# gambar.net
KiCad netlist of a schematic drawn in EAGLE
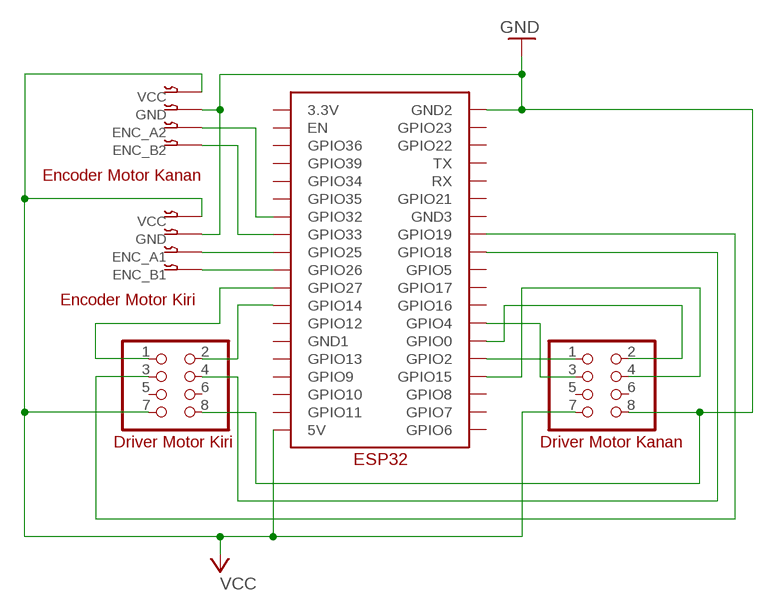
[diagram p0: schematic, sheet 1]

(export (version "E")
  (design (tool "Eeschema 10.0.6"))
  (components
    (comp (ref "DRIV1")
      (value "PINHD-2X4")
      (footprint "eagle-import:2X04")
      (libsource (lib "eagle-import") (part "PINHD-2X4"))
    )
    (comp (ref "DRIV2")
      (value "PINHD-2X4")
      (footprint "eagle-import:2X04")
      (libsource (lib "eagle-import") (part "PINHD-2X4"))
    )
    (comp (ref "U$1")
      (value "ESP32_GRBL")
      (footprint "eagle-import:ESP32_GRBL")
      (libsource (lib "eagle-import") (part "ESP32_GRBL"))
    )
    (comp (ref "X1")
      (value "ENC1")
      (footprint "eagle-import:B4B-XH")
      (libsource (lib "eagle-import") (part "04-JST-B4B-XH-A"))
    )
    (comp (ref "X2")
      (value "ENC2")
      (footprint "eagle-import:B4B-XH")
      (libsource (lib "eagle-import") (part "04-JST-B4B-XH-A"))
    )
  )
  (nets
    (net (code "1") (name "/ENC_A1") (class "Default")
      (node (ref "U$1") (pin "GPIO25") (pinfunction "GPIO25_GPIO25") (pintype "bidirectional"))
      (node (ref "X2") (pin "P$3") (pinfunction "1_P$3") (pintype "passive"))
    )
    (net (code "2") (name "/ENC_A2") (class "Default")
      (node (ref "U$1") (pin "GPIO32") (pinfunction "GPIO32_GPIO32") (pintype "bidirectional"))
      (node (ref "X1") (pin "P$3") (pinfunction "1_P$3") (pintype "passive"))
    )
    (net (code "3") (name "/ENC_B1") (class "Default")
      (node (ref "U$1") (pin "GPIO26") (pinfunction "GPIO26_GPIO26") (pintype "bidirectional"))
      (node (ref "X2") (pin "P$4") (pinfunction "1_P$4") (pintype "passive"))
    )
    (net (code "4") (name "/ENC_B2") (class "Default")
      (node (ref "U$1") (pin "GPIO33") (pinfunction "GPIO33_GPIO33") (pintype "bidirectional"))
      (node (ref "X1") (pin "P$4") (pinfunction "1_P$4") (pintype "passive"))
    )
    (net (code "5") (name "GND") (class "Default")
      (node (ref "DRIV1") (pin "8") (pinfunction "8_8") (pintype "passive"))
      (node (ref "DRIV2") (pin "8") (pinfunction "8_8") (pintype "passive"))
      (node (ref "U$1") (pin "GND2") (pinfunction "GND2_GND2") (pintype "bidirectional"))
      (node (ref "X1") (pin "P$2") (pinfunction "1_P$2") (pintype "passive"))
      (node (ref "X2") (pin "P$2") (pinfunction "1_P$2") (pintype "passive"))
    )
    (net (code "6") (name "Net-(DRIV1-Pad1)") (class "Default")
      (node (ref "DRIV1") (pin "1") (pinfunction "1_1") (pintype "passive"))
      (node (ref "U$1") (pin "GPIO27") (pinfunction "GPIO27_GPIO27") (pintype "bidirectional"))
    )
    (net (code "7") (name "Net-(DRIV1-Pad2)") (class "Default")
      (node (ref "DRIV1") (pin "2") (pinfunction "2_2") (pintype "passive"))
      (node (ref "U$1") (pin "GPIO14") (pinfunction "GPIO14_GPIO14") (pintype "bidirectional"))
    )
    (net (code "8") (name "Net-(DRIV1-Pad3)") (class "Default")
      (node (ref "DRIV1") (pin "3") (pinfunction "3_3") (pintype "passive"))
      (node (ref "U$1") (pin "GPIO19") (pinfunction "GPIO19_GPIO19") (pintype "bidirectional"))
    )
    (net (code "9") (name "Net-(DRIV1-Pad4)") (class "Default")
      (node (ref "DRIV1") (pin "4") (pinfunction "4_4") (pintype "passive"))
      (node (ref "U$1") (pin "GPIO18") (pinfunction "GPIO18_GPIO18") (pintype "bidirectional"))
    )
    (net (code "10") (name "Net-(DRIV2-Pad1)") (class "Default")
      (node (ref "DRIV2") (pin "1") (pinfunction "1_1") (pintype "passive"))
      (node (ref "U$1") (pin "GPIO2") (pinfunction "GPIO2_GPIO2") (pintype "bidirectional"))
    )
    (net (code "11") (name "Net-(DRIV2-Pad2)") (class "Default")
      (node (ref "DRIV2") (pin "2") (pinfunction "2_2") (pintype "passive"))
      (node (ref "U$1") (pin "GPIO0") (pinfunction "GPIO0_GPIO0") (pintype "bidirectional"))
    )
    (net (code "12") (name "Net-(DRIV2-Pad3)") (class "Default")
      (node (ref "DRIV2") (pin "3") (pinfunction "3_3") (pintype "passive"))
      (node (ref "U$1") (pin "GPIO4") (pinfunction "GPIO4_GPIO4") (pintype "bidirectional"))
    )
    (net (code "13") (name "Net-(DRIV2-Pad4)") (class "Default")
      (node (ref "DRIV2") (pin "4") (pinfunction "4_4") (pintype "passive"))
      (node (ref "U$1") (pin "GPIO15") (pinfunction "GPIO15_GPIO15") (pintype "bidirectional"))
    )
    (net (code "14") (name "VCC") (class "Default")
      (node (ref "DRIV1") (pin "7") (pinfunction "7_7") (pintype "passive"))
      (node (ref "DRIV2") (pin "7") (pinfunction "7_7") (pintype "passive"))
      (node (ref "U$1") (pin "5V") (pinfunction "5V_5V") (pintype "bidirectional"))
      (node (ref "X1") (pin "P$1") (pinfunction "1_P$1") (pintype "passive"))
      (node (ref "X2") (pin "P$1") (pinfunction "1_P$1") (pintype "passive"))
    )
    (net (code "15") (name "unconnected-(DRIV1-Pad5)") (class "Default")
      (node (ref "DRIV1") (pin "5") (pinfunction "5_5") (pintype "passive"))
    )
    (net (code "16") (name "unconnected-(DRIV1-Pad6)") (class "Default")
      (node (ref "DRIV1") (pin "6") (pinfunction "6_6") (pintype "passive"))
    )
    (net (code "17") (name "unconnected-(DRIV2-Pad5)") (class "Default")
      (node (ref "DRIV2") (pin "5") (pinfunction "5_5") (pintype "passive"))
    )
    (net (code "18") (name "unconnected-(DRIV2-Pad6)") (class "Default")
      (node (ref "DRIV2") (pin "6") (pinfunction "6_6") (pintype "passive"))
    )
    (net (code "19") (name "unconnected-(U$1-Pad3.3V)") (class "Default")
      (node (ref "U$1") (pin "3.3V") (pinfunction "3.3V_3.3V") (pintype "bidirectional"))
    )
    (net (code "20") (name "unconnected-(U$1-PadEN)") (class "Default")
      (node (ref "U$1") (pin "EN") (pinfunction "EN_EN") (pintype "bidirectional"))
    )
    (net (code "21") (name "unconnected-(U$1-PadGND1)") (class "Default")
      (node (ref "U$1") (pin "GND1") (pinfunction "GND1_GND1") (pintype "bidirectional"))
    )
    (net (code "22") (name "unconnected-(U$1-PadGND3)") (class "Default")
      (node (ref "U$1") (pin "GND3") (pinfunction "GND3_GND3") (pintype "bidirectional"))
    )
    (net (code "23") (name "unconnected-(U$1-PadGPIO5)") (class "Default")
      (node (ref "U$1") (pin "GPIO5") (pinfunction "GPIO5_GPIO5") (pintype "bidirectional"))
    )
    (net (code "24") (name "unconnected-(U$1-PadGPIO6)") (class "Default")
      (node (ref "U$1") (pin "GPIO6") (pinfunction "GPIO6_GPIO6") (pintype "bidirectional"))
    )
    (net (code "25") (name "unconnected-(U$1-PadGPIO7)") (class "Default")
      (node (ref "U$1") (pin "GPIO7") (pinfunction "GPIO7_GPIO7") (pintype "bidirectional"))
    )
    (net (code "26") (name "unconnected-(U$1-PadGPIO8)") (class "Default")
      (node (ref "U$1") (pin "GPIO8") (pinfunction "GPIO8_GPIO8") (pintype "bidirectional"))
    )
    (net (code "27") (name "unconnected-(U$1-PadGPIO9)") (class "Default")
      (node (ref "U$1") (pin "GPIO9") (pinfunction "GPIO9_GPIO9") (pintype "bidirectional"))
    )
    (net (code "28") (name "unconnected-(U$1-PadGPIO10)") (class "Default")
      (node (ref "U$1") (pin "GPIO10") (pinfunction "GPIO10_GPIO10") (pintype "bidirectional"))
    )
    (net (code "29") (name "unconnected-(U$1-PadGPIO11)") (class "Default")
      (node (ref "U$1") (pin "GPIO11") (pinfunction "GPIO11_GPIO11") (pintype "bidirectional"))
    )
    (net (code "30") (name "unconnected-(U$1-PadGPIO12)") (class "Default")
      (node (ref "U$1") (pin "GPIO12") (pinfunction "GPIO12_GPIO12") (pintype "bidirectional"))
    )
    (net (code "31") (name "unconnected-(U$1-PadGPIO13)") (class "Default")
      (node (ref "U$1") (pin "GPIO13") (pinfunction "GPIO13_GPIO13") (pintype "bidirectional"))
    )
    (net (code "32") (name "unconnected-(U$1-PadGPIO16)") (class "Default")
      (node (ref "U$1") (pin "GPIO16") (pinfunction "GPIO16_GPIO16") (pintype "bidirectional"))
    )
    (net (code "33") (name "unconnected-(U$1-PadGPIO17)") (class "Default")
      (node (ref "U$1") (pin "GPIO17") (pinfunction "GPIO17_GPIO17") (pintype "bidirectional"))
    )
    (net (code "34") (name "unconnected-(U$1-PadGPIO21)") (class "Default")
      (node (ref "U$1") (pin "GPIO21") (pinfunction "GPIO21_GPIO21") (pintype "bidirectional"))
    )
    (net (code "35") (name "unconnected-(U$1-PadGPIO22)") (class "Default")
      (node (ref "U$1") (pin "GPIO22") (pinfunction "GPIO22_GPIO22") (pintype "bidirectional"))
    )
    (net (code "36") (name "unconnected-(U$1-PadGPIO23)") (class "Default")
      (node (ref "U$1") (pin "GPIO23") (pinfunction "GPIO23_GPIO23") (pintype "bidirectional"))
    )
    (net (code "37") (name "unconnected-(U$1-PadGPIO34)") (class "Default")
      (node (ref "U$1") (pin "GPIO34") (pinfunction "GPIO34_GPIO34") (pintype "bidirectional"))
    )
    (net (code "38") (name "unconnected-(U$1-PadGPIO35)") (class "Default")
      (node (ref "U$1") (pin "GPIO35") (pinfunction "GPIO35_GPIO35") (pintype "bidirectional"))
    )
    (net (code "39") (name "unconnected-(U$1-PadGPIO36)") (class "Default")
      (node (ref "U$1") (pin "GPIO36") (pinfunction "GPIO36_GPIO36") (pintype "bidirectional"))
    )
    (net (code "40") (name "unconnected-(U$1-PadGPIO39)") (class "Default")
      (node (ref "U$1") (pin "GPIO39") (pinfunction "GPIO39_GPIO39") (pintype "bidirectional"))
    )
    (net (code "41") (name "unconnected-(U$1-PadRX)") (class "Default")
      (node (ref "U$1") (pin "RX") (pinfunction "RX_RX") (pintype "bidirectional"))
    )
    (net (code "42") (name "unconnected-(U$1-PadTX)") (class "Default")
      (node (ref "U$1") (pin "TX") (pinfunction "TX_TX") (pintype "bidirectional"))
    )
  )
)
